# supply.net
KiCad netlist of a schematic drawn in Altium Designer
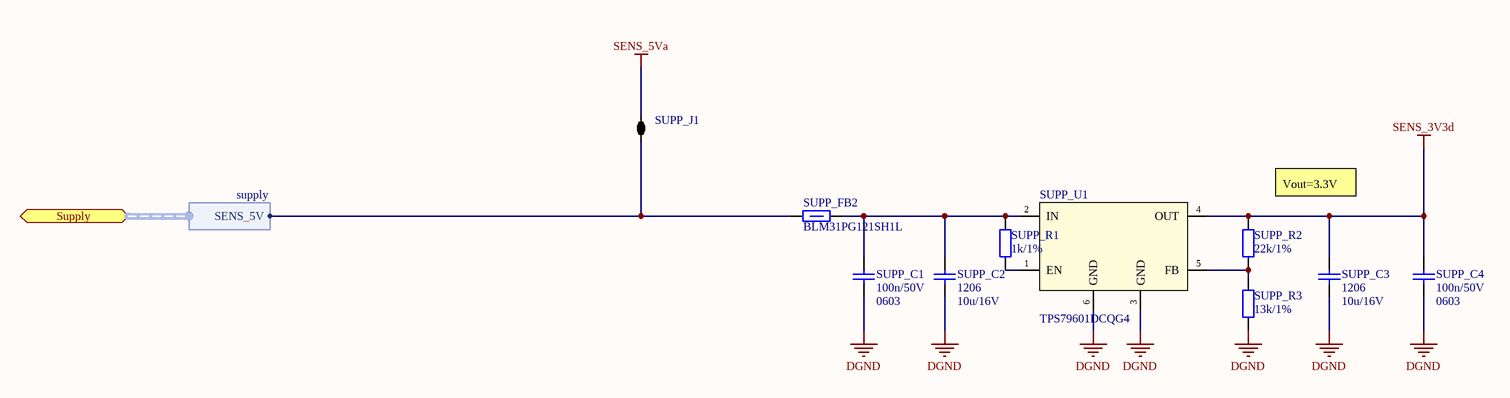
[diagram p0: supply.SchDoc]

(export (version "E")
  (design (tool "Eeschema 10.0.6"))
  (components
    (comp (ref "SUPP_C1")
      (value "100n/50V")
      (footprint "SMD_Capacitor_0603")
      (description "Ceramic Cap Kemet COTS 100n/50V X7R 0603")
      (fields
        (field (name "MANUFACTURER") "Kemet")
        (field (name "MANUFACTURERPARTNUMBER") "C0603T104K5RALTU")
        (field (name "PACKAGE") "0603")
      )
      (libsource (lib "capacitors") (part "Cer_C0603T104K5RALTU"))
    )
    (comp (ref "SUPP_C2")
      (value "10u/16V")
      (footprint "SMD_Capacitor_1206")
      (description "Ceramic Cap Kemet COTS 10u/16V X7R 1206")
      (fields
        (field (name "MANUFACTURERPARTNUMBER") "C1206T106K4RACTU")
        (field (name "MANUFACTURER") "Kemet")
        (field (name "PACKGE") "1206")
      )
      (libsource (lib "capacitors") (part "Cer_C1206T106K4RACTU"))
    )
    (comp (ref "SUPP_C3")
      (value "10u/16V")
      (footprint "SMD_Capacitor_1206")
      (description "Ceramic Cap Kemet COTS 10u/16V X7R 1206")
      (fields
        (field (name "MANUFACTURERPARTNUMBER") "C1206T106K4RACTU")
        (field (name "MANUFACTURER") "Kemet")
        (field (name "PACKGE") "1206")
      )
      (libsource (lib "capacitors") (part "Cer_C1206T106K4RACTU"))
    )
    (comp (ref "SUPP_C4")
      (value "100n/50V")
      (footprint "SMD_Capacitor_0603")
      (description "Ceramic Cap Kemet COTS 100n/50V X7R 0603")
      (fields
        (field (name "MANUFACTURER") "Kemet")
        (field (name "MANUFACTURERPARTNUMBER") "C0603T104K5RALTU")
        (field (name "PACKAGE") "0603")
      )
      (libsource (lib "capacitors") (part "Cer_C0603T104K5RALTU"))
    )
    (comp (ref "SUPP_FB2")
      (value "120R/100MHz")
      (footprint "SMD_FerriteBead_1206")
      (description "Ferrite bead, 1206, 0.02HM, 3.5A.")
      (fields (field (name "MANUFACTURER") "Murata") (field (name "MANUFACTURERPARTNUMBER") "BLM31PG121SH1L"))
      (libsource (lib "inductors") (part "BLM31PG121SH1L"))
    )
    (comp (ref "SUPP_J1")
      (value "2 way net tie junction")
      (footprint "2way_LP")
      (libsource (lib "NetTieLib") (part "2way"))
    )
    (comp (ref "SUPP_R1")
      (value "1k/1%")
      (footprint "SMD_Resistor_0603")
      (description "1k/1% Vishay CRCW 0603 Resistor. 100mW, 100ppm, 75V.")
      (fields
        (field (name "MANUFACTURER") "Vishay")
        (field (name "MANUFACTURERPARTNUMBER") "CRCW06031K00FKxxxx")
      )
      (libsource (lib "resistors") (part "CRCW06031K00FKxxxx"))
    )
    (comp (ref "SUPP_R2")
      (value "22k/1%")
      (footprint "SMD_Resistor_0603")
      (libsource (lib "resistors") (part "Res"))
    )
    (comp (ref "SUPP_R3")
      (value "13k/1%")
      (footprint "SMD_Resistor_0603")
      (libsource (lib "resistors") (part "Res"))
    )
    (comp (ref "SUPP_U1")
      (value "~")
      (footprint "TI-DCQ")
      (description "1A, Ajdustable LDO, Ultralow-Noise, High PSRR, Fast, RF")
      (fields
        (field (name "MANUFACTURER") "Texas Instruments")
        (field (name "MANUFACTURERPARTNUMBER") "TPS79601DCQG4")
      )
      (libsource (lib "microcircuits") (part "TPS79601DCQG4"))
    )
  )
  (nets
    (net (code "3") (name "DGND") (class "Default")
      (node (ref "SUPP_C1") (pin "2") (pinfunction "2_2") (pintype "passive"))
      (node (ref "SUPP_C2") (pin "2") (pinfunction "2_2") (pintype "passive"))
      (node (ref "SUPP_C3") (pin "2") (pinfunction "2_2") (pintype "passive"))
      (node (ref "SUPP_C4") (pin "2") (pinfunction "2_2") (pintype "passive"))
      (node (ref "SUPP_R3") (pin "2") (pinfunction "2_2") (pintype "passive"))
      (node (ref "SUPP_U1") (pin "3") (pinfunction "GND_3") (pintype "passive"))
      (node (ref "SUPP_U1") (pin "6") (pinfunction "GND_6") (pintype "passive"))
    )
    (net (code "4") (name "Net-(SUPP_FB2-Pad1)") (class "Default")
      (node (ref "SUPP_FB2") (pin "1") (pinfunction "1_1") (pintype "passive"))
      (node (ref "SUPP_J1") (pin "1") (pinfunction "1_1") (pintype "passive"))
    )
    (net (code "5") (name "Net-(SUPP_U1-EN)") (class "Default")
      (node (ref "SUPP_R1") (pin "2") (pinfunction "2_2") (pintype "passive"))
      (node (ref "SUPP_U1") (pin "1") (pinfunction "EN_1") (pintype "passive"))
    )
    (net (code "6") (name "Net-(SUPP_U1-FB)") (class "Default")
      (node (ref "SUPP_R2") (pin "2") (pinfunction "2_2") (pintype "passive"))
      (node (ref "SUPP_R3") (pin "1") (pinfunction "1_1") (pintype "passive"))
      (node (ref "SUPP_U1") (pin "5") (pinfunction "FB_5") (pintype "passive"))
    )
    (net (code "7") (name "Net-(SUPP_U1-IN)") (class "Default")
      (node (ref "SUPP_C1") (pin "1") (pinfunction "1_1") (pintype "passive"))
      (node (ref "SUPP_C2") (pin "1") (pinfunction "1_1") (pintype "passive"))
      (node (ref "SUPP_FB2") (pin "2") (pinfunction "2_2") (pintype "passive"))
      (node (ref "SUPP_R1") (pin "1") (pinfunction "1_1") (pintype "passive"))
      (node (ref "SUPP_U1") (pin "2") (pinfunction "IN_2") (pintype "passive"))
    )
    (net (code "8") (name "SENS_3V3d") (class "Default")
      (node (ref "SUPP_C3") (pin "1") (pinfunction "1_1") (pintype "passive"))
      (node (ref "SUPP_C4") (pin "1") (pinfunction "1_1") (pintype "passive"))
      (node (ref "SUPP_R2") (pin "1") (pinfunction "1_1") (pintype "passive"))
      (node (ref "SUPP_U1") (pin "4") (pinfunction "OUT_4") (pintype "passive"))
    )
    (net (code "9") (name "SENS_5Va") (class "Default")
      (node (ref "SUPP_J1") (pin "2") (pinfunction "2_2") (pintype "passive"))
    )
  )
)
